# scanner.net
KiCad netlist of a schematic drawn in EAGLE
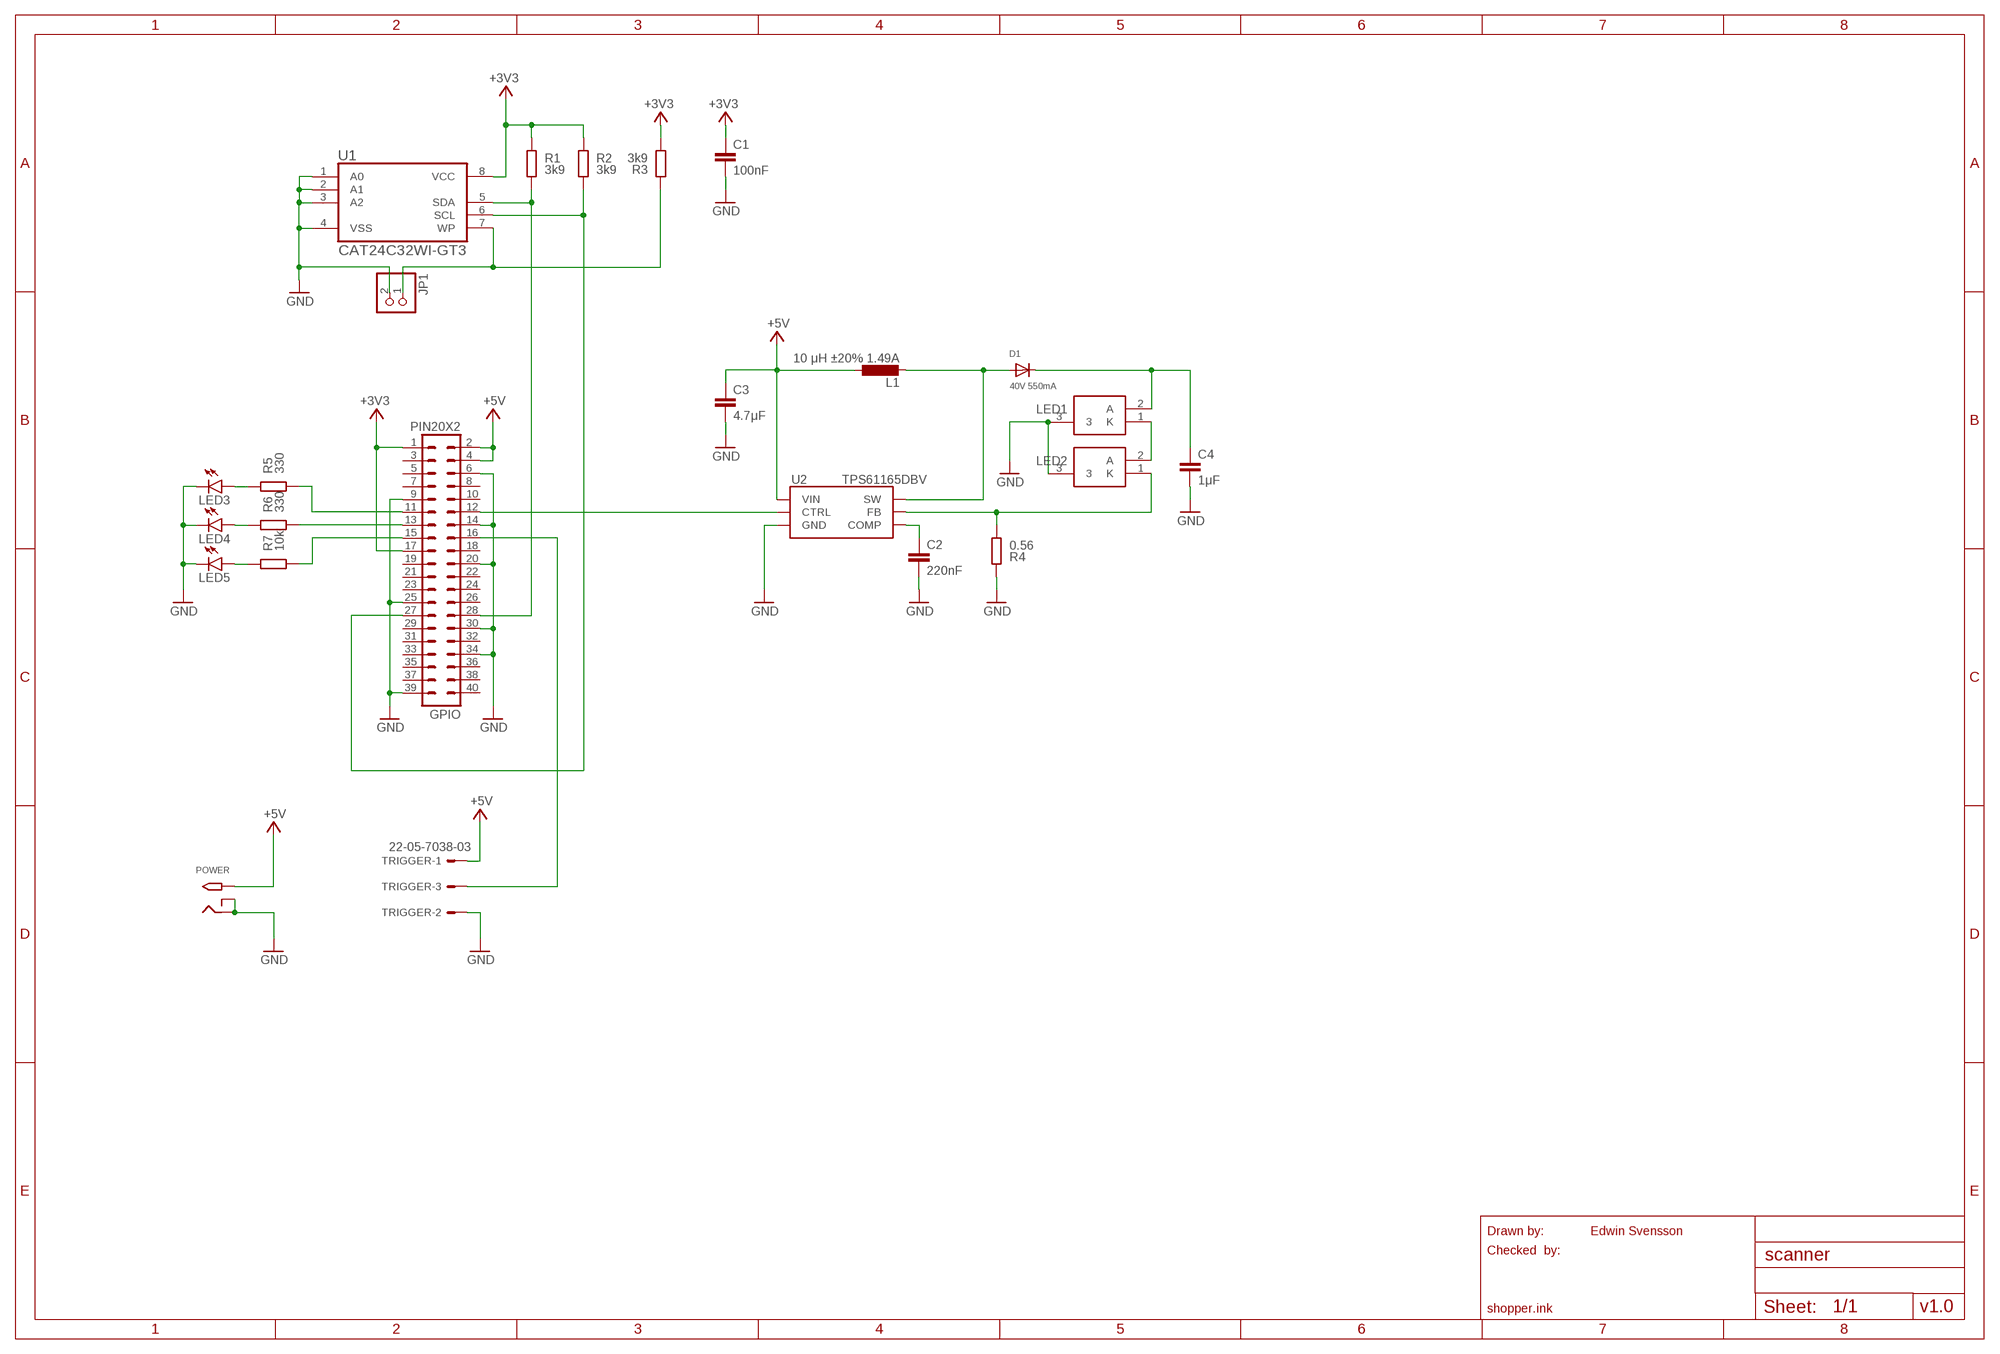
[diagram p0: schematic, sheet 1]

(export (version "E")
  (design (tool "Eeschema 10.0.6"))
  (components
    (comp (ref "C1")
      (value "100nF")
      (footprint "eagle-import:C0805K")
      (libsource (lib "eagle-import") (part "C-EUC0805K"))
    )
    (comp (ref "C2")
      (value "220nF")
      (footprint "eagle-import:C0805K")
      (libsource (lib "eagle-import") (part "C-EUC0805K"))
    )
    (comp (ref "C3")
      (value "4.7μF")
      (footprint "eagle-import:C0805K")
      (libsource (lib "eagle-import") (part "C-EUC0805K"))
    )
    (comp (ref "C4")
      (value "1μF")
      (footprint "eagle-import:C0805K")
      (libsource (lib "eagle-import") (part "C-EUC0805K"))
    )
    (comp (ref "D1")
      (value "40V 550mA")
      (footprint "eagle-import:SOD-123")
      (libsource (lib "eagle-import") (part "DIODESOD-123"))
    )
    (comp (ref "GPIO")
      (value "PIN20X2")
      (footprint "eagle-import:PIN_20X2")
      (libsource (lib "eagle-import") (part "PIN20X2"))
    )
    (comp (ref "JP1")
      (value "PINHD-1X2")
      (footprint "eagle-import:1X02")
      (libsource (lib "eagle-import") (part "PINHD-1X2"))
    )
    (comp (ref "L1")
      (value "10 μH ±20% 1.49A")
      (footprint "eagle-import:D53LC")
      (libsource (lib "eagle-import") (part "D53LC"))
    )
    (comp (ref "LED1")
      (value "LW_W5SM-JYKY-JKQL-1")
      (footprint "eagle-import:LWW5SMJYKYJKQL1")
      (fields
        (field (name "MANUFACTURER_PART_NUMBER") "LW W5SM-JYKY-JKQL-1")
        (field (name "MOUSER_PART_NUMBER") "720-LWW5SMJYKYJKQL1")
      )
      (libsource (lib "eagle-import") (part "LW_W5SM-JYKY-JKQL-1"))
    )
    (comp (ref "LED2")
      (value "LW_W5SM-JYKY-JKQL-1")
      (footprint "eagle-import:LWW5SMJYKYJKQL1")
      (fields
        (field (name "MANUFACTURER_PART_NUMBER") "LW W5SM-JYKY-JKQL-1")
        (field (name "MOUSER_PART_NUMBER") "720-LWW5SMJYKYJKQL1")
      )
      (libsource (lib "eagle-import") (part "LW_W5SM-JYKY-JKQL-1"))
    )
    (comp (ref "LED3")
      (value "LEDCHIP-LED0805")
      (footprint "eagle-import:CHIP-LED0805")
      (libsource (lib "eagle-import") (part "LEDCHIP-LED0805"))
    )
    (comp (ref "LED4")
      (value "LEDCHIP-LED0805")
      (footprint "eagle-import:CHIP-LED0805")
      (libsource (lib "eagle-import") (part "LEDCHIP-LED0805"))
    )
    (comp (ref "LED5")
      (value "LEDCHIP-LED0805")
      (footprint "eagle-import:CHIP-LED0805")
      (libsource (lib "eagle-import") (part "LEDCHIP-LED0805"))
    )
    (comp (ref "POWER")
      (value "2.1MMJACKTHM")
      (footprint "eagle-import:PJ-102A")
      (libsource (lib "eagle-import") (part "2.1MMJACKTHM"))
    )
    (comp (ref "R1")
      (value "3k9")
      (footprint "eagle-import:M0805")
      (fields (field (name "TOLERANCE") "5%"))
      (libsource (lib "eagle-import") (part "R-EU_M0805"))
    )
    (comp (ref "R2")
      (value "3k9")
      (footprint "eagle-import:M0805")
      (fields (field (name "TOLERANCE") "5%"))
      (libsource (lib "eagle-import") (part "R-EU_M0805"))
    )
    (comp (ref "R3")
      (value "3k9")
      (footprint "eagle-import:M0805")
      (fields (field (name "TOLERANCE") "5%"))
      (libsource (lib "eagle-import") (part "R-EU_M0805"))
    )
    (comp (ref "R4")
      (value "0.56")
      (footprint "eagle-import:M0805")
      (fields (field (name "TOLERANCE") "5%"))
      (libsource (lib "eagle-import") (part "R-EU_M0805"))
    )
    (comp (ref "R5")
      (value "330")
      (footprint "eagle-import:M0805")
      (fields (field (name "TOLERANCE") "5%"))
      (libsource (lib "eagle-import") (part "R-EU_M0805"))
    )
    (comp (ref "R6")
      (value "330")
      (footprint "eagle-import:M0805")
      (fields (field (name "TOLERANCE") "5%"))
      (libsource (lib "eagle-import") (part "R-EU_M0805"))
    )
    (comp (ref "R7")
      (value "10k")
      (footprint "eagle-import:M0805")
      (fields (field (name "TOLERANCE") "5%"))
      (libsource (lib "eagle-import") (part "R-EU_M0805"))
    )
    (comp (ref "TRIGGER")
      (value "22-05-7038-03")
      (footprint "eagle-import:7395-03")
      (fields (field (name "MF") "MOLEX"))
      (libsource (lib "eagle-import") (part "22-?-0305-7038"))
    )
    (comp (ref "U1")
      (value "CAT24C32WI-GT3")
      (footprint "eagle-import:SOIC127P600X175-8N")
      (libsource (lib "eagle-import") (part "CAT24C32WI-GT3"))
    )
    (comp (ref "U2")
      (value "TPS61165DBV")
      (footprint "eagle-import:SOT-23-6")
      (libsource (lib "eagle-import") (part "TPS61165DBV"))
    )
  )
  (nets
    (net (code "1") (name "+3V3") (class "Default")
      (node (ref "C1") (pin "1") (pinfunction "1_1") (pintype "passive"))
      (node (ref "GPIO") (pin "1") (pinfunction "1_1") (pintype "passive"))
      (node (ref "GPIO") (pin "17") (pinfunction "17_17") (pintype "passive"))
      (node (ref "R1") (pin "2") (pinfunction "2_2") (pintype "passive"))
      (node (ref "R2") (pin "2") (pinfunction "2_2") (pintype "passive"))
      (node (ref "R3") (pin "1") (pinfunction "1_1") (pintype "passive"))
      (node (ref "U1") (pin "8") (pinfunction "VCC_8") (pintype "passive"))
    )
    (net (code "2") (name "+5V") (class "Default")
      (node (ref "C3") (pin "1") (pinfunction "1_1") (pintype "passive"))
      (node (ref "GPIO") (pin "2") (pinfunction "2_2") (pintype "passive"))
      (node (ref "GPIO") (pin "4") (pinfunction "4_4") (pintype "passive"))
      (node (ref "L1") (pin "1") (pinfunction "1_1") (pintype "passive"))
      (node (ref "POWER") (pin "TIP") (pinfunction "TIP_TIP") (pintype "bidirectional"))
      (node (ref "TRIGGER") (pin "1") (pinfunction "S_1") (pintype "passive"))
      (node (ref "U2") (pin "1") (pinfunction "VIN_1") (pintype "power_in"))
    )
    (net (code "3") (name "GND") (class "Default")
      (node (ref "C1") (pin "2") (pinfunction "2_2") (pintype "passive"))
      (node (ref "C2") (pin "2") (pinfunction "2_2") (pintype "passive"))
      (node (ref "C3") (pin "2") (pinfunction "2_2") (pintype "passive"))
      (node (ref "C4") (pin "2") (pinfunction "2_2") (pintype "passive"))
      (node (ref "GPIO") (pin "14") (pinfunction "14_14") (pintype "passive"))
      (node (ref "GPIO") (pin "20") (pinfunction "20_20") (pintype "passive"))
      (node (ref "GPIO") (pin "25") (pinfunction "25_25") (pintype "passive"))
      (node (ref "GPIO") (pin "30") (pinfunction "30_30") (pintype "passive"))
      (node (ref "GPIO") (pin "34") (pinfunction "34_34") (pintype "passive"))
      (node (ref "GPIO") (pin "39") (pinfunction "39_39") (pintype "passive"))
      (node (ref "GPIO") (pin "6") (pinfunction "6_6") (pintype "passive"))
      (node (ref "GPIO") (pin "9") (pinfunction "9_9") (pintype "passive"))
      (node (ref "JP1") (pin "2") (pinfunction "2_2") (pintype "passive"))
      (node (ref "LED1") (pin "3") (pinfunction "3_3") (pintype "bidirectional"))
      (node (ref "LED2") (pin "3") (pinfunction "3_3") (pintype "bidirectional"))
      (node (ref "LED3") (pin "C") (pinfunction "C_C") (pintype "passive"))
      (node (ref "LED4") (pin "C") (pinfunction "C_C") (pintype "passive"))
      (node (ref "LED5") (pin "C") (pinfunction "C_C") (pintype "passive"))
      (node (ref "POWER") (pin "RING") (pinfunction "RING_RING") (pintype "bidirectional"))
      (node (ref "POWER") (pin "RING_SW") (pinfunction "RING_SW_RING_SW") (pintype "bidirectional"))
      (node (ref "R4") (pin "2") (pinfunction "2_2") (pintype "passive"))
      (node (ref "TRIGGER") (pin "2") (pinfunction "S_2") (pintype "passive"))
      (node (ref "U1") (pin "1") (pinfunction "A0_1") (pintype "input"))
      (node (ref "U1") (pin "2") (pinfunction "A1_2") (pintype "input"))
      (node (ref "U1") (pin "3") (pinfunction "A2_3") (pintype "input"))
      (node (ref "U1") (pin "4") (pinfunction "VSS_4") (pintype "passive"))
      (node (ref "U2") (pin "4") (pinfunction "GND_4") (pintype "power_in"))
    )
    (net (code "4") (name "Net-(GPIO-Pad11)") (class "Default")
      (node (ref "GPIO") (pin "11") (pinfunction "11_11") (pintype "passive"))
      (node (ref "R5") (pin "1") (pinfunction "1_1") (pintype "passive"))
    )
    (net (code "5") (name "Net-(GPIO-Pad13)") (class "Default")
      (node (ref "GPIO") (pin "13") (pinfunction "13_13") (pintype "passive"))
      (node (ref "R6") (pin "1") (pinfunction "1_1") (pintype "passive"))
    )
    (net (code "6") (name "Net-(GPIO-Pad15)") (class "Default")
      (node (ref "GPIO") (pin "15") (pinfunction "15_15") (pintype "passive"))
      (node (ref "R7") (pin "1") (pinfunction "1_1") (pintype "passive"))
    )
    (net (code "7") (name "Net-(LED1-A)") (class "Default")
      (node (ref "C4") (pin "1") (pinfunction "1_1") (pintype "passive"))
      (node (ref "D1") (pin "C") (pinfunction "C_C") (pintype "passive"))
      (node (ref "LED1") (pin "2") (pinfunction "A_2") (pintype "bidirectional"))
    )
    (net (code "8") (name "Net-(LED1-K)") (class "Default")
      (node (ref "LED1") (pin "1") (pinfunction "K_1") (pintype "bidirectional"))
      (node (ref "LED2") (pin "2") (pinfunction "A_2") (pintype "bidirectional"))
    )
    (net (code "9") (name "Net-(LED2-K)") (class "Default")
      (node (ref "LED2") (pin "1") (pinfunction "K_1") (pintype "bidirectional"))
      (node (ref "R4") (pin "1") (pinfunction "1_1") (pintype "passive"))
      (node (ref "U2") (pin "6") (pinfunction "FB_6") (pintype "input"))
    )
    (net (code "10") (name "Net-(LED3-PadA)") (class "Default")
      (node (ref "LED3") (pin "A") (pinfunction "A_A") (pintype "passive"))
      (node (ref "R5") (pin "2") (pinfunction "2_2") (pintype "passive"))
    )
    (net (code "11") (name "Net-(LED4-PadA)") (class "Default")
      (node (ref "LED4") (pin "A") (pinfunction "A_A") (pintype "passive"))
      (node (ref "R6") (pin "2") (pinfunction "2_2") (pintype "passive"))
    )
    (net (code "12") (name "Net-(LED5-PadA)") (class "Default")
      (node (ref "LED5") (pin "A") (pinfunction "A_A") (pintype "passive"))
      (node (ref "R7") (pin "2") (pinfunction "2_2") (pintype "passive"))
    )
    (net (code "13") (name "Net-(TRIGGERC-S)") (class "Default")
      (node (ref "GPIO") (pin "16") (pinfunction "16_16") (pintype "passive"))
      (node (ref "TRIGGER") (pin "3") (pinfunction "S_3") (pintype "passive"))
    )
    (net (code "14") (name "Net-(U1-SCL)") (class "Default")
      (node (ref "GPIO") (pin "27") (pinfunction "27_27") (pintype "passive"))
      (node (ref "R2") (pin "1") (pinfunction "1_1") (pintype "passive"))
      (node (ref "U1") (pin "6") (pinfunction "SCL_6") (pintype "input"))
    )
    (net (code "15") (name "Net-(U1-SDA)") (class "Default")
      (node (ref "GPIO") (pin "28") (pinfunction "28_28") (pintype "passive"))
      (node (ref "R1") (pin "1") (pinfunction "1_1") (pintype "passive"))
      (node (ref "U1") (pin "5") (pinfunction "SDA_5") (pintype "bidirectional"))
    )
    (net (code "16") (name "Net-(U1-WP)") (class "Default")
      (node (ref "JP1") (pin "1") (pinfunction "1_1") (pintype "passive"))
      (node (ref "R3") (pin "2") (pinfunction "2_2") (pintype "passive"))
      (node (ref "U1") (pin "7") (pinfunction "WP_7") (pintype "input"))
    )
    (net (code "17") (name "Net-(U2-COMP)") (class "Default")
      (node (ref "C2") (pin "1") (pinfunction "1_1") (pintype "passive"))
      (node (ref "U2") (pin "5") (pinfunction "COMP_5") (pintype "output"))
    )
    (net (code "18") (name "Net-(U2-CTRL)") (class "Default")
      (node (ref "GPIO") (pin "12") (pinfunction "12_12") (pintype "passive"))
      (node (ref "U2") (pin "2") (pinfunction "CTRL_2") (pintype "input"))
    )
    (net (code "19") (name "Net-(U2-SW)") (class "Default")
      (node (ref "D1") (pin "A") (pinfunction "A_A") (pintype "passive"))
      (node (ref "L1") (pin "2") (pinfunction "2_2") (pintype "passive"))
      (node (ref "U2") (pin "3") (pinfunction "SW_3") (pintype "output"))
    )
    (net (code "20") (name "unconnected-(GPIO-Pad3)") (class "Default")
      (node (ref "GPIO") (pin "3") (pinfunction "3_3") (pintype "passive"))
    )
    (net (code "21") (name "unconnected-(GPIO-Pad5)") (class "Default")
      (node (ref "GPIO") (pin "5") (pinfunction "5_5") (pintype "passive"))
    )
    (net (code "22") (name "unconnected-(GPIO-Pad7)") (class "Default")
      (node (ref "GPIO") (pin "7") (pinfunction "7_7") (pintype "passive"))
    )
    (net (code "23") (name "unconnected-(GPIO-Pad8)") (class "Default")
      (node (ref "GPIO") (pin "8") (pinfunction "8_8") (pintype "passive"))
    )
    (net (code "24") (name "unconnected-(GPIO-Pad10)") (class "Default")
      (node (ref "GPIO") (pin "10") (pinfunction "10_10") (pintype "passive"))
    )
    (net (code "25") (name "unconnected-(GPIO-Pad18)") (class "Default")
      (node (ref "GPIO") (pin "18") (pinfunction "18_18") (pintype "passive"))
    )
    (net (code "26") (name "unconnected-(GPIO-Pad19)") (class "Default")
      (node (ref "GPIO") (pin "19") (pinfunction "19_19") (pintype "passive"))
    )
    (net (code "27") (name "unconnected-(GPIO-Pad21)") (class "Default")
      (node (ref "GPIO") (pin "21") (pinfunction "21_21") (pintype "passive"))
    )
    (net (code "28") (name "unconnected-(GPIO-Pad22)") (class "Default")
      (node (ref "GPIO") (pin "22") (pinfunction "22_22") (pintype "passive"))
    )
    (net (code "29") (name "unconnected-(GPIO-Pad23)") (class "Default")
      (node (ref "GPIO") (pin "23") (pinfunction "23_23") (pintype "passive"))
    )
    (net (code "30") (name "unconnected-(GPIO-Pad24)") (class "Default")
      (node (ref "GPIO") (pin "24") (pinfunction "24_24") (pintype "passive"))
    )
    (net (code "31") (name "unconnected-(GPIO-Pad26)") (class "Default")
      (node (ref "GPIO") (pin "26") (pinfunction "26_26") (pintype "passive"))
    )
    (net (code "32") (name "unconnected-(GPIO-Pad29)") (class "Default")
      (node (ref "GPIO") (pin "29") (pinfunction "29_29") (pintype "passive"))
    )
    (net (code "33") (name "unconnected-(GPIO-Pad31)") (class "Default")
      (node (ref "GPIO") (pin "31") (pinfunction "31_31") (pintype "passive"))
    )
    (net (code "34") (name "unconnected-(GPIO-Pad32)") (class "Default")
      (node (ref "GPIO") (pin "32") (pinfunction "32_32") (pintype "passive"))
    )
    (net (code "35") (name "unconnected-(GPIO-Pad33)") (class "Default")
      (node (ref "GPIO") (pin "33") (pinfunction "33_33") (pintype "passive"))
    )
    (net (code "36") (name "unconnected-(GPIO-Pad35)") (class "Default")
      (node (ref "GPIO") (pin "35") (pinfunction "35_35") (pintype "passive"))
    )
    (net (code "37") (name "unconnected-(GPIO-Pad36)") (class "Default")
      (node (ref "GPIO") (pin "36") (pinfunction "36_36") (pintype "passive"))
    )
    (net (code "38") (name "unconnected-(GPIO-Pad37)") (class "Default")
      (node (ref "GPIO") (pin "37") (pinfunction "37_37") (pintype "passive"))
    )
    (net (code "39") (name "unconnected-(GPIO-Pad38)") (class "Default")
      (node (ref "GPIO") (pin "38") (pinfunction "38_38") (pintype "passive"))
    )
    (net (code "40") (name "unconnected-(GPIO-Pad40)") (class "Default")
      (node (ref "GPIO") (pin "40") (pinfunction "40_40") (pintype "passive"))
    )
  )
)
